# power_converter.net
KiCad netlist of a schematic drawn in EAGLE
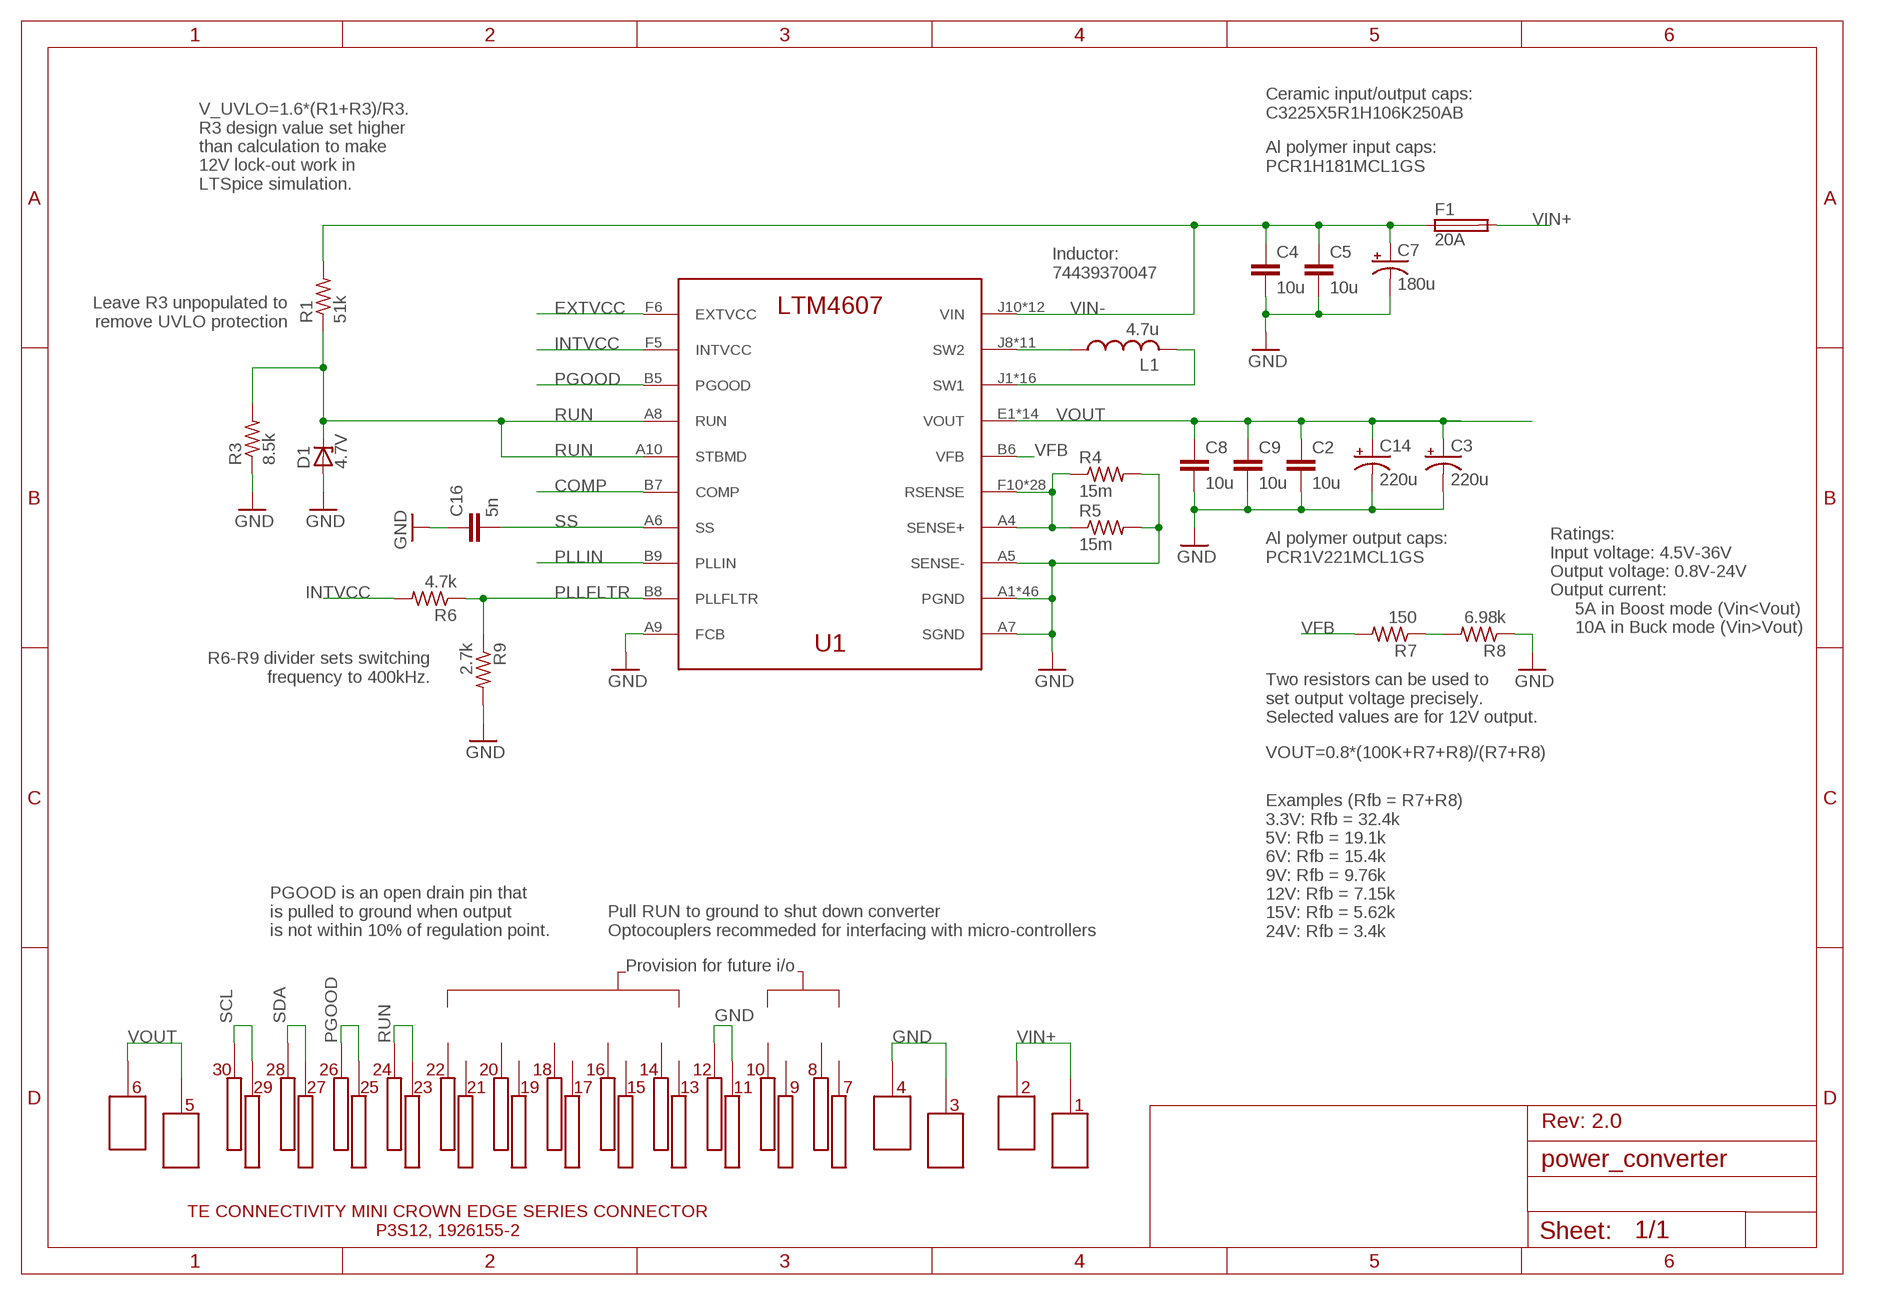
[diagram p0: schematic, sheet 1]

(export (version "E")
  (design (tool "Eeschema 10.0.6"))
  (components
    (comp (ref "C2")
      (value "10u")
      (footprint "eagle-import:C1210")
      (libsource (lib "eagle-import") (part "C-EUC1210"))
    )
    (comp (ref "C3")
      (value "220u")
      (footprint "eagle-import:PCR1V221MCL1GS")
      (libsource (lib "eagle-import") (part "PCR1V221MCL1GS"))
    )
    (comp (ref "C4")
      (value "10u")
      (footprint "eagle-import:C1210")
      (libsource (lib "eagle-import") (part "C-EUC1210"))
    )
    (comp (ref "C5")
      (value "10u")
      (footprint "eagle-import:C1210")
      (libsource (lib "eagle-import") (part "C-EUC1210"))
    )
    (comp (ref "C7")
      (value "180u")
      (footprint "eagle-import:PCR1H181MCL1GS")
      (libsource (lib "eagle-import") (part "PCR1H181MCL1GS"))
    )
    (comp (ref "C8")
      (value "10u")
      (footprint "eagle-import:C1210")
      (libsource (lib "eagle-import") (part "C-EUC1210"))
    )
    (comp (ref "C9")
      (value "10u")
      (footprint "eagle-import:C1210")
      (libsource (lib "eagle-import") (part "C-EUC1210"))
    )
    (comp (ref "C14")
      (value "220u")
      (footprint "eagle-import:PCR1V221MCL1GS")
      (libsource (lib "eagle-import") (part "PCR1V221MCL1GS"))
    )
    (comp (ref "C16")
      (value "5n")
      (footprint "eagle-import:C0603")
      (libsource (lib "eagle-import") (part "C-EUC0603"))
    )
    (comp (ref "D1")
      (value "4.7V")
      (footprint "eagle-import:SOD80C")
      (libsource (lib "eagle-import") (part "ZENER-DIODESOD80C"))
    )
    (comp (ref "F1")
      (value "20A")
      (footprint "eagle-import:R1206")
      (libsource (lib "eagle-import") (part "501_FUSE"))
    )
    (comp (ref "L1")
      (value "4.7u")
      (footprint "eagle-import:PA4343.472ANLT")
      (libsource (lib "eagle-import") (part "PA4343.472ANLT"))
    )
    (comp (ref "R1")
      (value "51k")
      (footprint "eagle-import:R0603")
      (libsource (lib "eagle-import") (part "R-US_R0603"))
    )
    (comp (ref "R3")
      (value "8.5k")
      (footprint "eagle-import:R0603")
      (libsource (lib "eagle-import") (part "R-US_R0603"))
    )
    (comp (ref "R4")
      (value "15m")
      (footprint "eagle-import:R1206")
      (libsource (lib "eagle-import") (part "R-US_R1206"))
    )
    (comp (ref "R5")
      (value "15m")
      (footprint "eagle-import:R1206")
      (libsource (lib "eagle-import") (part "R-US_R1206"))
    )
    (comp (ref "R6")
      (value "4.7k")
      (footprint "eagle-import:R0603")
      (libsource (lib "eagle-import") (part "R-US_R0603"))
    )
    (comp (ref "R7")
      (value "150")
      (footprint "eagle-import:R0603")
      (libsource (lib "eagle-import") (part "R-US_R0603"))
    )
    (comp (ref "R8")
      (value "6.98k")
      (footprint "eagle-import:R0603")
      (libsource (lib "eagle-import") (part "R-US_R0603"))
    )
    (comp (ref "R9")
      (value "2.7k")
      (footprint "eagle-import:R0603")
      (libsource (lib "eagle-import") (part "R-US_R0603"))
    )
    (comp (ref "U$1")
      (value "1926155-2_CARD")
      (footprint "eagle-import:1926155-2_CARD")
      (libsource (lib "eagle-import") (part "1926155-2_CARD"))
    )
    (comp (ref "U1")
      (value "LTM4607EVPBF")
      (footprint "eagle-import:LGA-141")
      (fields (field (name "MANUFACTURER_PART_NUMBER") "LTM4607EV#PBF"))
      (libsource (lib "eagle-import") (part "LTM4607EVPBF"))
    )
  )
  (nets
    (net (code "1") (name "/COMP") (class "Default")
      (node (ref "U1") (pin "B7") (pinfunction "COMP_B7") (pintype "power_in"))
    )
    (net (code "2") (name "/EXTVCC") (class "Default")
      (node (ref "U1") (pin "F6") (pinfunction "EXTVCC_F6") (pintype "power_in"))
    )
    (net (code "3") (name "/INTVCC") (class "Default")
      (node (ref "R6") (pin "2") (pinfunction "2_2") (pintype "passive"))
      (node (ref "U1") (pin "F5") (pinfunction "INTVCC_F5") (pintype "power_in"))
    )
    (net (code "4") (name "/PGOOD") (class "Default")
      (node (ref "U$1") (pin "P$25") (pinfunction "P$25_P$25") (pintype "bidirectional"))
      (node (ref "U$1") (pin "P$26") (pinfunction "P$26_P$26") (pintype "bidirectional"))
      (node (ref "U1") (pin "B5") (pinfunction "PGOOD_B5") (pintype "power_in"))
    )
    (net (code "5") (name "/PLLFLTR") (class "Default")
      (node (ref "R6") (pin "1") (pinfunction "1_1") (pintype "passive"))
      (node (ref "R9") (pin "1") (pinfunction "1_1") (pintype "passive"))
      (node (ref "U1") (pin "B8") (pinfunction "PLLFLTR_B8") (pintype "power_in"))
    )
    (net (code "6") (name "/PLLIN") (class "Default")
      (node (ref "U1") (pin "B9") (pinfunction "PLLIN_B9") (pintype "power_in"))
    )
    (net (code "7") (name "/RUN") (class "Default")
      (node (ref "D1") (pin "C") (pinfunction "C_C") (pintype "passive"))
      (node (ref "R1") (pin "1") (pinfunction "1_1") (pintype "passive"))
      (node (ref "R3") (pin "2") (pinfunction "2_2") (pintype "passive"))
      (node (ref "U$1") (pin "P$23") (pinfunction "P$23_P$23") (pintype "bidirectional"))
      (node (ref "U$1") (pin "P$24") (pinfunction "P$24_P$24") (pintype "bidirectional"))
      (node (ref "U1") (pin "A10") (pinfunction "STBMD_A10") (pintype "power_in"))
      (node (ref "U1") (pin "A8") (pinfunction "RUN_A8") (pintype "power_in"))
    )
    (net (code "8") (name "/SCL") (class "Default")
      (node (ref "U$1") (pin "P$29") (pinfunction "P$29_P$29") (pintype "bidirectional"))
      (node (ref "U$1") (pin "P$30") (pinfunction "P$30_P$30") (pintype "bidirectional"))
    )
    (net (code "9") (name "/SDA") (class "Default")
      (node (ref "U$1") (pin "P$27") (pinfunction "P$27_P$27") (pintype "bidirectional"))
      (node (ref "U$1") (pin "P$28") (pinfunction "P$28_P$28") (pintype "bidirectional"))
    )
    (net (code "10") (name "/SS") (class "Default")
      (node (ref "C16") (pin "2") (pinfunction "2_2") (pintype "passive"))
      (node (ref "U1") (pin "A6") (pinfunction "SS_A6") (pintype "power_in"))
    )
    (net (code "11") (name "/VFB") (class "Default")
      (node (ref "R7") (pin "2") (pinfunction "2_2") (pintype "passive"))
      (node (ref "U1") (pin "B6") (pinfunction "VFB_B6") (pintype "power_in"))
    )
    (net (code "12") (name "/VIN+") (class "Default")
      (node (ref "F1") (pin "2") (pinfunction "2_2") (pintype "passive"))
      (node (ref "U$1") (pin "P$1") (pinfunction "P$1_P$1") (pintype "bidirectional"))
      (node (ref "U$1") (pin "P$2") (pinfunction "P$2_P$2") (pintype "bidirectional"))
    )
    (net (code "13") (name "/VIN-") (class "Default")
      (node (ref "C4") (pin "1") (pinfunction "1_1") (pintype "passive"))
      (node (ref "C5") (pin "1") (pinfunction "1_1") (pintype "passive"))
      (node (ref "C7") (pin "POS") (pinfunction "+_POS") (pintype "passive"))
      (node (ref "F1") (pin "1") (pinfunction "1_1") (pintype "passive"))
      (node (ref "R1") (pin "2") (pinfunction "2_2") (pintype "passive"))
      (node (ref "U1") (pin "J10") (pinfunction "VIN_J10") (pintype "power_in"))
      (node (ref "U1") (pin "J11") (pinfunction "VIN_J11") (pintype "power_in"))
      (node (ref "U1") (pin "J12") (pinfunction "VIN_J12") (pintype "power_in"))
      (node (ref "U1") (pin "K10") (pinfunction "VIN_K10") (pintype "power_in"))
      (node (ref "U1") (pin "K11") (pinfunction "VIN_K11") (pintype "power_in"))
      (node (ref "U1") (pin "K12") (pinfunction "VIN_K12") (pintype "power_in"))
      (node (ref "U1") (pin "L10") (pinfunction "VIN_L10") (pintype "power_in"))
      (node (ref "U1") (pin "L11") (pinfunction "VIN_L11") (pintype "power_in"))
      (node (ref "U1") (pin "L12") (pinfunction "VIN_L12") (pintype "power_in"))
      (node (ref "U1") (pin "M10") (pinfunction "VIN_M10") (pintype "power_in"))
      (node (ref "U1") (pin "M11") (pinfunction "VIN_M11") (pintype "power_in"))
      (node (ref "U1") (pin "M12") (pinfunction "VIN_M12") (pintype "power_in"))
    )
    (net (code "14") (name "/VOUT") (class "Default")
      (node (ref "C14") (pin "POS") (pinfunction "+_POS") (pintype "passive"))
      (node (ref "C2") (pin "1") (pinfunction "1_1") (pintype "passive"))
      (node (ref "C3") (pin "POS") (pinfunction "+_POS") (pintype "passive"))
      (node (ref "C8") (pin "1") (pinfunction "1_1") (pintype "passive"))
      (node (ref "C9") (pin "1") (pinfunction "1_1") (pintype "passive"))
      (node (ref "U$1") (pin "P$5") (pinfunction "P$5_P$5") (pintype "bidirectional"))
      (node (ref "U$1") (pin "P$6") (pinfunction "P$6_P$6") (pintype "bidirectional"))
      (node (ref "U1") (pin "E1") (pinfunction "VOUT_E1") (pintype "power_in"))
      (node (ref "U1") (pin "E2") (pinfunction "VOUT_E2") (pintype "power_in"))
      (node (ref "U1") (pin "F1") (pinfunction "VOUT_F1") (pintype "power_in"))
      (node (ref "U1") (pin "F2") (pinfunction "VOUT_F2") (pintype "power_in"))
      (node (ref "U1") (pin "F3") (pinfunction "VOUT_F3") (pintype "power_in"))
      (node (ref "U1") (pin "F4") (pinfunction "VOUT_F4") (pintype "power_in"))
      (node (ref "U1") (pin "G1") (pinfunction "VOUT_G1") (pintype "power_in"))
      (node (ref "U1") (pin "G2") (pinfunction "VOUT_G2") (pintype "power_in"))
      (node (ref "U1") (pin "G3") (pinfunction "VOUT_G3") (pintype "power_in"))
      (node (ref "U1") (pin "G4") (pinfunction "VOUT_G4") (pintype "power_in"))
      (node (ref "U1") (pin "H1") (pinfunction "VOUT_H1") (pintype "power_in"))
      (node (ref "U1") (pin "H2") (pinfunction "VOUT_H2") (pintype "power_in"))
      (node (ref "U1") (pin "H3") (pinfunction "VOUT_H3") (pintype "power_in"))
      (node (ref "U1") (pin "H4") (pinfunction "VOUT_H4") (pintype "power_in"))
    )
    (net (code "15") (name "GND") (class "Default")
      (node (ref "C14") (pin "NEG") (pinfunction "-_NEG") (pintype "passive"))
      (node (ref "C16") (pin "1") (pinfunction "1_1") (pintype "passive"))
      (node (ref "C2") (pin "2") (pinfunction "2_2") (pintype "passive"))
      (node (ref "C3") (pin "NEG") (pinfunction "-_NEG") (pintype "passive"))
      (node (ref "C4") (pin "2") (pinfunction "2_2") (pintype "passive"))
      (node (ref "C5") (pin "2") (pinfunction "2_2") (pintype "passive"))
      (node (ref "C7") (pin "NEG") (pinfunction "-_NEG") (pintype "passive"))
      (node (ref "C8") (pin "2") (pinfunction "2_2") (pintype "passive"))
      (node (ref "C9") (pin "2") (pinfunction "2_2") (pintype "passive"))
      (node (ref "D1") (pin "A") (pinfunction "A_A") (pintype "passive"))
      (node (ref "R3") (pin "1") (pinfunction "1_1") (pintype "passive"))
      (node (ref "R4") (pin "2") (pinfunction "2_2") (pintype "passive"))
      (node (ref "R5") (pin "2") (pinfunction "2_2") (pintype "passive"))
      (node (ref "R8") (pin "1") (pinfunction "1_1") (pintype "passive"))
      (node (ref "R9") (pin "2") (pinfunction "2_2") (pintype "passive"))
      (node (ref "U$1") (pin "P$11") (pinfunction "P$11_P$11") (pintype "bidirectional"))
      (node (ref "U$1") (pin "P$12") (pinfunction "P$12_P$12") (pintype "bidirectional"))
      (node (ref "U$1") (pin "P$3") (pinfunction "P$3_P$3") (pintype "bidirectional"))
      (node (ref "U$1") (pin "P$4") (pinfunction "P$4_P$4") (pintype "bidirectional"))
      (node (ref "U1") (pin "A1") (pinfunction "PGND_A1") (pintype "power_in"))
      (node (ref "U1") (pin "A11") (pinfunction "PGND_A11") (pintype "power_in"))
      (node (ref "U1") (pin "A12") (pinfunction "PGND_A12") (pintype "power_in"))
      (node (ref "U1") (pin "A2") (pinfunction "PGND_A2") (pintype "power_in"))
      (node (ref "U1") (pin "A3") (pinfunction "PGND_A3") (pintype "power_in"))
      (node (ref "U1") (pin "A5") (pinfunction "SENSE-_A5") (pintype "power_in"))
      (node (ref "U1") (pin "A7") (pinfunction "SGND_A7") (pintype "power_in"))
      (node (ref "U1") (pin "A9") (pinfunction "FCB_A9") (pintype "power_in"))
      (node (ref "U1") (pin "B1") (pinfunction "PGND_B1") (pintype "power_in"))
      (node (ref "U1") (pin "B10") (pinfunction "PGND_B10") (pintype "power_in"))
      (node (ref "U1") (pin "B11") (pinfunction "PGND_B11") (pintype "power_in"))
      (node (ref "U1") (pin "B12") (pinfunction "PGND_B12") (pintype "power_in"))
      (node (ref "U1") (pin "B2") (pinfunction "PGND_B2") (pintype "power_in"))
      (node (ref "U1") (pin "B3") (pinfunction "PGND_B3") (pintype "power_in"))
      (node (ref "U1") (pin "B4") (pinfunction "PGND_B4") (pintype "power_in"))
      (node (ref "U1") (pin "C1") (pinfunction "PGND_C1") (pintype "power_in"))
      (node (ref "U1") (pin "C10") (pinfunction "PGND_C10") (pintype "power_in"))
      (node (ref "U1") (pin "C11") (pinfunction "PGND_C11") (pintype "power_in"))
      (node (ref "U1") (pin "C12") (pinfunction "PGND_C12") (pintype "power_in"))
      (node (ref "U1") (pin "C2") (pinfunction "PGND_C2") (pintype "power_in"))
      (node (ref "U1") (pin "C3") (pinfunction "PGND_C3") (pintype "power_in"))
      (node (ref "U1") (pin "C4") (pinfunction "PGND_C4") (pintype "power_in"))
      (node (ref "U1") (pin "C5") (pinfunction "PGND_C5") (pintype "power_in"))
      (node (ref "U1") (pin "C6") (pinfunction "PGND_C6") (pintype "power_in"))
      (node (ref "U1") (pin "C7") (pinfunction "PGND_C7") (pintype "power_in"))
      (node (ref "U1") (pin "C8") (pinfunction "PGND_C8") (pintype "power_in"))
      (node (ref "U1") (pin "C9") (pinfunction "PGND_C9") (pintype "power_in"))
      (node (ref "U1") (pin "D1") (pinfunction "PGND_D1") (pintype "power_in"))
      (node (ref "U1") (pin "D10") (pinfunction "PGND_D10") (pintype "power_in"))
      (node (ref "U1") (pin "D11") (pinfunction "PGND_D11") (pintype "power_in"))
      (node (ref "U1") (pin "D12") (pinfunction "PGND_D12") (pintype "power_in"))
      (node (ref "U1") (pin "D2") (pinfunction "PGND_D2") (pintype "power_in"))
      (node (ref "U1") (pin "D3") (pinfunction "PGND_D3") (pintype "power_in"))
      (node (ref "U1") (pin "D4") (pinfunction "PGND_D4") (pintype "power_in"))
      (node (ref "U1") (pin "D5") (pinfunction "PGND_D5") (pintype "power_in"))
      (node (ref "U1") (pin "D6") (pinfunction "PGND_D6") (pintype "power_in"))
      (node (ref "U1") (pin "D7") (pinfunction "PGND_D7") (pintype "power_in"))
      (node (ref "U1") (pin "D8") (pinfunction "PGND_D8") (pintype "power_in"))
      (node (ref "U1") (pin "D9") (pinfunction "PGND_D9") (pintype "power_in"))
      (node (ref "U1") (pin "E10") (pinfunction "PGND_E10") (pintype "power_in"))
      (node (ref "U1") (pin "E11") (pinfunction "PGND_E11") (pintype "power_in"))
      (node (ref "U1") (pin "E12") (pinfunction "PGND_E12") (pintype "power_in"))
      (node (ref "U1") (pin "E3") (pinfunction "PGND_E3") (pintype "power_in"))
      (node (ref "U1") (pin "E4") (pinfunction "PGND_E4") (pintype "power_in"))
      (node (ref "U1") (pin "E5") (pinfunction "PGND_E5") (pintype "power_in"))
      (node (ref "U1") (pin "E6") (pinfunction "PGND_E6") (pintype "power_in"))
      (node (ref "U1") (pin "E7") (pinfunction "PGND_E7") (pintype "power_in"))
      (node (ref "U1") (pin "E8") (pinfunction "PGND_E8") (pintype "power_in"))
      (node (ref "U1") (pin "E9") (pinfunction "PGND_E9") (pintype "power_in"))
    )
    (net (code "16") (name "Net-(L1-1)") (class "Default")
      (node (ref "L1") (pin "P$1") (pinfunction "1_P$1") (pintype "passive"))
      (node (ref "U1") (pin "J8") (pinfunction "SW2_J8") (pintype "power_in"))
      (node (ref "U1") (pin "J9") (pinfunction "SW2_J9") (pintype "power_in"))
      (node (ref "U1") (pin "K7") (pinfunction "SW2_K7") (pintype "power_in"))
      (node (ref "U1") (pin "K8") (pinfunction "SW2_K8") (pintype "power_in"))
      (node (ref "U1") (pin "K9") (pinfunction "SW2_K9") (pintype "power_in"))
      (node (ref "U1") (pin "L7") (pinfunction "SW2_L7") (pintype "power_in"))
      (node (ref "U1") (pin "L8") (pinfunction "SW2_L8") (pintype "power_in"))
      (node (ref "U1") (pin "L9") (pinfunction "SW2_L9") (pintype "power_in"))
      (node (ref "U1") (pin "M7") (pinfunction "SW2_M7") (pintype "power_in"))
      (node (ref "U1") (pin "M8") (pinfunction "SW2_M8") (pintype "power_in"))
      (node (ref "U1") (pin "M9") (pinfunction "SW2_M9") (pintype "power_in"))
    )
    (net (code "17") (name "Net-(L1-2)") (class "Default")
      (node (ref "L1") (pin "P$2") (pinfunction "2_P$2") (pintype "passive"))
      (node (ref "U1") (pin "J1") (pinfunction "SW1_J1") (pintype "power_in"))
      (node (ref "U1") (pin "J2") (pinfunction "SW1_J2") (pintype "power_in"))
      (node (ref "U1") (pin "J3") (pinfunction "SW1_J3") (pintype "power_in"))
      (node (ref "U1") (pin "J4") (pinfunction "SW1_J4") (pintype "power_in"))
      (node (ref "U1") (pin "K1") (pinfunction "SW1_K1") (pintype "power_in"))
      (node (ref "U1") (pin "K2") (pinfunction "SW1_K2") (pintype "power_in"))
      (node (ref "U1") (pin "K3") (pinfunction "SW1_K3") (pintype "power_in"))
      (node (ref "U1") (pin "K4") (pinfunction "SW1_K4") (pintype "power_in"))
      (node (ref "U1") (pin "L1") (pinfunction "SW1_L1") (pintype "power_in"))
      (node (ref "U1") (pin "L2") (pinfunction "SW1_L2") (pintype "power_in"))
      (node (ref "U1") (pin "L3") (pinfunction "SW1_L3") (pintype "power_in"))
      (node (ref "U1") (pin "L4") (pinfunction "SW1_L4") (pintype "power_in"))
      (node (ref "U1") (pin "M1") (pinfunction "SW1_M1") (pintype "power_in"))
      (node (ref "U1") (pin "M2") (pinfunction "SW1_M2") (pintype "power_in"))
      (node (ref "U1") (pin "M3") (pinfunction "SW1_M3") (pintype "power_in"))
      (node (ref "U1") (pin "M4") (pinfunction "SW1_M4") (pintype "power_in"))
    )
    (net (code "18") (name "Net-(R7-Pad1)") (class "Default")
      (node (ref "R7") (pin "1") (pinfunction "1_1") (pintype "passive"))
      (node (ref "R8") (pin "2") (pinfunction "2_2") (pintype "passive"))
    )
    (net (code "19") (name "Net-(U1-SENSE+)") (class "Default")
      (node (ref "R4") (pin "1") (pinfunction "1_1") (pintype "passive"))
      (node (ref "R5") (pin "1") (pinfunction "1_1") (pintype "passive"))
      (node (ref "U1") (pin "A4") (pinfunction "SENSE+_A4") (pintype "power_in"))
      (node (ref "U1") (pin "F10") (pinfunction "RSENSE_F10") (pintype "power_in"))
      (node (ref "U1") (pin "F11") (pinfunction "RSENSE_F11") (pintype "power_in"))
      (node (ref "U1") (pin "F12") (pinfunction "RSENSE_F12") (pintype "power_in"))
      (node (ref "U1") (pin "G10") (pinfunction "RSENSE_G10") (pintype "power_in"))
      (node (ref "U1") (pin "G11") (pinfunction "RSENSE_G11") (pintype "power_in"))
      (node (ref "U1") (pin "G12") (pinfunction "RSENSE_G12") (pintype "power_in"))
      (node (ref "U1") (pin "G5") (pinfunction "RSENSE_G5") (pintype "power_in"))
      (node (ref "U1") (pin "G6") (pinfunction "RSENSE_G6") (pintype "power_in"))
      (node (ref "U1") (pin "G7") (pinfunction "RSENSE_G7") (pintype "power_in"))
      (node (ref "U1") (pin "G8") (pinfunction "RSENSE_G8") (pintype "power_in"))
      (node (ref "U1") (pin "G9") (pinfunction "RSENSE_G9") (pintype "power_in"))
      (node (ref "U1") (pin "H10") (pinfunction "RSENSE_H10") (pintype "power_in"))
      (node (ref "U1") (pin "H11") (pinfunction "RSENSE_H11") (pintype "power_in"))
      (node (ref "U1") (pin "H12") (pinfunction "RSENSE_H12") (pintype "power_in"))
      (node (ref "U1") (pin "H5") (pinfunction "RSENSE_H5") (pintype "power_in"))
      (node (ref "U1") (pin "H6") (pinfunction "RSENSE_H6") (pintype "power_in"))
      (node (ref "U1") (pin "H7") (pinfunction "RSENSE_H7") (pintype "power_in"))
      (node (ref "U1") (pin "H8") (pinfunction "RSENSE_H8") (pintype "power_in"))
      (node (ref "U1") (pin "H9") (pinfunction "RSENSE_H9") (pintype "power_in"))
      (node (ref "U1") (pin "J5") (pinfunction "RSENSE_J5") (pintype "power_in"))
      (node (ref "U1") (pin "J6") (pinfunction "RSENSE_J6") (pintype "power_in"))
      (node (ref "U1") (pin "J7") (pinfunction "RSENSE_J7") (pintype "power_in"))
      (node (ref "U1") (pin "K5") (pinfunction "RSENSE_K5") (pintype "power_in"))
      (node (ref "U1") (pin "K6") (pinfunction "RSENSE_K6") (pintype "power_in"))
      (node (ref "U1") (pin "L5") (pinfunction "RSENSE_L5") (pintype "power_in"))
      (node (ref "U1") (pin "L6") (pinfunction "RSENSE_L6") (pintype "power_in"))
      (node (ref "U1") (pin "M5") (pinfunction "RSENSE_M5") (pintype "power_in"))
      (node (ref "U1") (pin "M6") (pinfunction "RSENSE_M6") (pintype "power_in"))
    )
    (net (code "20") (name "unconnected-(U$1-PadP$7)") (class "Default")
      (node (ref "U$1") (pin "P$7") (pinfunction "P$7_P$7") (pintype "bidirectional"))
    )
    (net (code "21") (name "unconnected-(U$1-PadP$8)") (class "Default")
      (node (ref "U$1") (pin "P$8") (pinfunction "P$8_P$8") (pintype "bidirectional"))
    )
    (net (code "22") (name "unconnected-(U$1-PadP$9)") (class "Default")
      (node (ref "U$1") (pin "P$9") (pinfunction "P$9_P$9") (pintype "bidirectional"))
    )
    (net (code "23") (name "unconnected-(U$1-PadP$10)") (class "Default")
      (node (ref "U$1") (pin "P$10") (pinfunction "P$10_P$10") (pintype "bidirectional"))
    )
    (net (code "24") (name "unconnected-(U$1-PadP$13)") (class "Default")
      (node (ref "U$1") (pin "P$13") (pinfunction "P$13_P$13") (pintype "bidirectional"))
    )
    (net (code "25") (name "unconnected-(U$1-PadP$14)") (class "Default")
      (node (ref "U$1") (pin "P$14") (pinfunction "P$14_P$14") (pintype "bidirectional"))
    )
    (net (code "26") (name "unconnected-(U$1-PadP$15)") (class "Default")
      (node (ref "U$1") (pin "P$15") (pinfunction "P$15_P$15") (pintype "bidirectional"))
    )
    (net (code "27") (name "unconnected-(U$1-PadP$16)") (class "Default")
      (node (ref "U$1") (pin "P$16") (pinfunction "P$16_P$16") (pintype "bidirectional"))
    )
    (net (code "28") (name "unconnected-(U$1-PadP$17)") (class "Default")
      (node (ref "U$1") (pin "P$17") (pinfunction "P$17_P$17") (pintype "bidirectional"))
    )
    (net (code "29") (name "unconnected-(U$1-PadP$18)") (class "Default")
      (node (ref "U$1") (pin "P$18") (pinfunction "P$18_P$18") (pintype "bidirectional"))
    )
    (net (code "30") (name "unconnected-(U$1-PadP$19)") (class "Default")
      (node (ref "U$1") (pin "P$19") (pinfunction "P$19_P$19") (pintype "bidirectional"))
    )
    (net (code "31") (name "unconnected-(U$1-PadP$20)") (class "Default")
      (node (ref "U$1") (pin "P$20") (pinfunction "P$20_P$20") (pintype "bidirectional"))
    )
    (net (code "32") (name "unconnected-(U$1-PadP$21)") (class "Default")
      (node (ref "U$1") (pin "P$21") (pinfunction "P$21_P$21") (pintype "bidirectional"))
    )
    (net (code "33") (name "unconnected-(U$1-PadP$22)") (class "Default")
      (node (ref "U$1") (pin "P$22") (pinfunction "P$22_P$22") (pintype "bidirectional"))
    )
  )
)
